# Voeding.net
KiCad netlist of a schematic drawn in Altium Designer
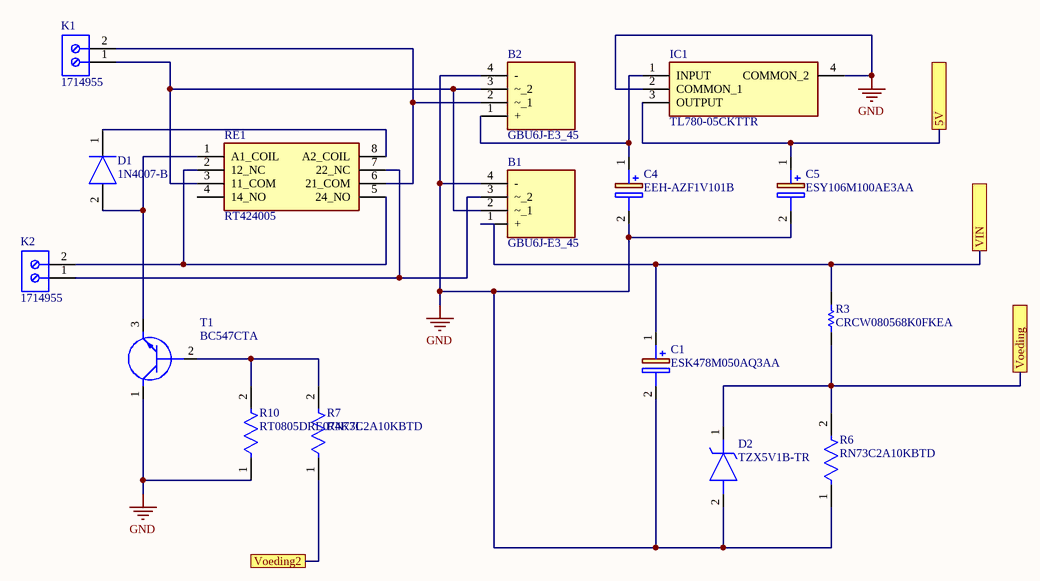
[diagram p0: Voeding.SchDoc]

(export (version "E")
  (design (tool "Eeschema 10.0.6"))
  (components
    (comp (ref "B1")
      (value "GBU6J-E3_45")
      (footprint "SamacSys:GBU6JE345")
      (description "Bridge Rectifier")
      (fields (field (name "MANUFACTURER_PART_NUMBER") "GBU6J-E3/45"))
      (libsource (lib "*") (part "GBU6J-E3_45"))
    )
    (comp (ref "B2")
      (value "GBU6J-E3_45")
      (footprint "SamacSys:GBU6JE345")
      (description "Bridge Rectifier")
      (fields (field (name "MANUFACTURER_PART_NUMBER") "GBU6J-E3/45"))
      (libsource (lib "*") (part "GBU6J-E3_45"))
    )
    (comp (ref "C1")
      (value "ESK478M050AQ3AA")
      (footprint "SamacSys:CAPPRD1000W80D2200H3700")
      (description "Capacitor Polarised")
      (fields (field (name "MOUSER2 PART NUMBER") "80-ESK478M050AQ3AA"))
      (libsource (lib "*") (part "ESK478M050AQ3AA"))
    )
    (comp (ref "C4")
      (value "EEH-AZF1V101B")
      (footprint "SamacSys:CAPPRD350W65D800H1050")
      (description "Capacitor Polarised")
      (libsource (lib "*") (part "EEH-AZF1V101B"))
    )
    (comp (ref "C5")
      (value "ESY106M100AE3AA")
      (footprint "SamacSys:CAPPRD250W50D630H1250")
      (description "Capacitor Polarised")
      (libsource (lib "*") (part "ESY106M100AE3AA"))
    )
    (comp (ref "D1")
      (value "1N4007-B")
      (footprint "SamacSys:DIOAD1410W90L470D235")
      (description "Diode")
      (libsource (lib "*") (part "1N4007-B"))
    )
    (comp (ref "D2")
      (value "TZX5V1B-TR")
      (footprint "SamacSys:DIOAD950W60L350D150")
      (description "Zener Diode")
      (libsource (lib "*") (part "TZX5V1B-TR"))
    )
    (comp (ref "IC1")
      (value "TL780-05CKTTR")
      (footprint "SamacSys:TL78005CKTTR")
      (description "Integrated Circuit")
      (libsource (lib "*") (part "TL780-05CKTTR"))
    )
    (comp (ref "K1")
      (value "1714955")
      (footprint "PHOE-1714955_V")
      (description "PC Terminal Block, Pitch 6.35 mm, 1 x 2 Position, Height 21.5 mm, Tail Lenght 5.1 mm, RoHS, Bulk")
      (fields (field (name "MANUFACTURER") "Phoenix Contact"))
      (libsource (lib "Altium Content Vault") (part "CN-1P-F-TB2"))
    )
    (comp (ref "K2")
      (value "1714955")
      (footprint "PHOE-1714955_V")
      (description "PC Terminal Block, Pitch 6.35 mm, 1 x 2 Position, Height 21.5 mm, Tail Lenght 5.1 mm, RoHS, Bulk")
      (fields (field (name "MANUFACTURER") "Phoenix Contact"))
      (libsource (lib "Altium Content Vault") (part "CN-1P-F-TB2"))
    )
    (comp (ref "R3")
      (value "CRCW080568K0FKEA")
      (footprint "RESC2013X50X30ML20T20")
      (fields (field (name "MANUFACTURER") "Vishay Dale"))
      (libsource (lib "Altium Content Vault") (part "RES"))
    )
    (comp (ref "R6")
      (value "RN73C2A10KBTD")
      (footprint "FP-RN732A-MFG")
      (description "SMD Chip Resistor, Thin Film, 10KΩ, 100 V, 0805 [2012 Metric], 100 mW, 0.1%, RN73 Series")
      (fields
        (field (name "MANUFACTURER") "TE Connectivity")
        (field (name "OCTOPART") "https://octopart.com/rn73c2a10kbtd-te+connectivity-22737006")
      )
      (libsource (lib "Altium Content Vault") (part "1029c3af85768c4190bb7ad29bc67b5"))
    )
    (comp (ref "R7")
      (value "RN73C2A10KBTD")
      (footprint "FP-RN732A-MFG")
      (description "SMD Chip Resistor, Thin Film, 10KΩ, 100 V, 0805 [2012 Metric], 100 mW, 0.1%, RN73 Series")
      (fields
        (field (name "MANUFACTURER") "TE Connectivity")
        (field (name "OCTOPART") "https://octopart.com/rn73c2a10kbtd-te+connectivity-22737006")
      )
      (libsource (lib "Altium Content Vault") (part "1029c3af85768c4190bb7ad29bc67b5"))
    )
    (comp (ref "R10")
      (value "RT0805DRE074K7L")
      (footprint "FP-RT0805-MFG")
      (description "RES SMD 4.7K OHM 0.5% 1/8W 0805")
      (fields
        (field (name "OCTOPART") "https://octopart.com/rt0805dre074k7l-yageo-1242027")
        (field (name "TOLERANCE") "0.01")
      )
      (libsource (lib "Altium Content Vault") (part "1029c3af85768c4190bb7ad29bc67b5"))
    )
    (comp (ref "RE1")
      (value "RT424005")
      (footprint "SamacSys:RT42")
      (description "Relay or Contactor")
      (fields (field (name "MOUSER2 PART NUMBER") "655-RT424005"))
      (libsource (lib "*") (part "RT424005"))
    )
    (comp (ref "T1")
      (value "BC547CTA")
      (footprint "SamacSys:MC79L15ACPG")
      (description "Transistor BJT NPN")
      (libsource (lib "*") (part "BC547CTA"))
    )
  )
  (nets
    (net (code "1") (name "/5V") (class "Default")
      (node (ref "C5") (pin "1") (pinfunction "+_1") (pintype "passive"))
      (node (ref "IC1") (pin "3") (pinfunction "OUTPUT_3") (pintype "passive"))
    )
    (net (code "2") (name "/VIN") (class "Default")
      (node (ref "B1") (pin "1") (pinfunction "+_1") (pintype "passive"))
      (node (ref "C1") (pin "1") (pinfunction "+_1") (pintype "passive"))
      (node (ref "R3") (pin "2") (pinfunction "2_2") (pintype "passive"))
    )
    (net (code "3") (name "/Voeding") (class "Default")
      (node (ref "D2") (pin "1") (pinfunction "K_1") (pintype "passive"))
      (node (ref "R3") (pin "1") (pinfunction "1_1") (pintype "passive"))
      (node (ref "R6") (pin "2") (pinfunction "2_2") (pintype "passive"))
    )
    (net (code "4") (name "/Voeding2") (class "Default")
      (node (ref "R7") (pin "1") (pinfunction "1_1") (pintype "passive"))
    )
    (net (code "5") (name "GND") (class "Default")
      (node (ref "B1") (pin "4") (pinfunction "-_4") (pintype "passive"))
      (node (ref "B2") (pin "4") (pinfunction "-_4") (pintype "passive"))
      (node (ref "C1") (pin "2") (pinfunction "-_2") (pintype "passive"))
      (node (ref "C4") (pin "2") (pinfunction "-_2") (pintype "passive"))
      (node (ref "C5") (pin "2") (pinfunction "-_2") (pintype "passive"))
      (node (ref "D2") (pin "2") (pinfunction "A_2") (pintype "passive"))
      (node (ref "IC1") (pin "2") (pinfunction "COMMON_1_2") (pintype "passive"))
      (node (ref "IC1") (pin "4") (pinfunction "COMMON_2_4") (pintype "passive"))
      (node (ref "R10") (pin "1") (pinfunction "1_1") (pintype "passive"))
      (node (ref "R6") (pin "1") (pinfunction "1_1") (pintype "passive"))
      (node (ref "T1") (pin "1") (pinfunction "C_1") (pintype "passive"))
    )
    (net (code "6") (name "Net-(B1-~_1)") (class "Default")
      (node (ref "B1") (pin "2") (pinfunction "~_1_2") (pintype "passive"))
      (node (ref "B2") (pin "3") (pinfunction "~_2_3") (pintype "passive"))
      (node (ref "K1") (pin "1") (pinfunction "1_1") (pintype "passive"))
      (node (ref "RE1") (pin "3") (pinfunction "11_COM_3") (pintype "passive"))
    )
    (net (code "7") (name "Net-(B1-~_2)") (class "Default")
      (node (ref "B1") (pin "3") (pinfunction "~_2_3") (pintype "passive"))
      (node (ref "K2") (pin "1") (pinfunction "1_1") (pintype "passive"))
      (node (ref "RE1") (pin "7") (pinfunction "22_NC_7") (pintype "passive"))
    )
    (net (code "8") (name "Net-(B2-+)") (class "Default")
      (node (ref "B2") (pin "1") (pinfunction "+_1") (pintype "passive"))
      (node (ref "C4") (pin "1") (pinfunction "+_1") (pintype "passive"))
      (node (ref "IC1") (pin "1") (pinfunction "INPUT_1") (pintype "passive"))
    )
    (net (code "9") (name "Net-(B2-~_1)") (class "Default")
      (node (ref "B2") (pin "2") (pinfunction "~_1_2") (pintype "passive"))
      (node (ref "K1") (pin "2") (pinfunction "2_2") (pintype "passive"))
      (node (ref "RE1") (pin "6") (pinfunction "21_COM_6") (pintype "passive"))
    )
    (net (code "10") (name "Net-(D1-A)") (class "Default")
      (node (ref "D1") (pin "2") (pinfunction "A_2") (pintype "passive"))
      (node (ref "RE1") (pin "1") (pinfunction "A1_COIL_1") (pintype "passive"))
      (node (ref "T1") (pin "3") (pinfunction "E_3") (pintype "passive"))
    )
    (net (code "11") (name "Net-(D1-K)") (class "Default")
      (node (ref "D1") (pin "1") (pinfunction "K_1") (pintype "passive"))
      (node (ref "RE1") (pin "8") (pinfunction "A2_COIL_8") (pintype "passive"))
    )
    (net (code "12") (name "Net-(RE1-12_NC)") (class "Default")
      (node (ref "K2") (pin "2") (pinfunction "2_2") (pintype "passive"))
      (node (ref "RE1") (pin "2") (pinfunction "12_NC_2") (pintype "passive"))
      (node (ref "RE1") (pin "5") (pinfunction "24_NO_5") (pintype "passive"))
    )
    (net (code "13") (name "Net-(T1-B)") (class "Default")
      (node (ref "R10") (pin "2") (pinfunction "2_2") (pintype "passive"))
      (node (ref "R7") (pin "2") (pinfunction "2_2") (pintype "passive"))
      (node (ref "T1") (pin "2") (pinfunction "B_2") (pintype "passive"))
    )
    (net (code "14") (name "unconnected-(RE1-14_NO-Pad4)") (class "Default")
      (node (ref "RE1") (pin "4") (pinfunction "14_NO_4") (pintype "passive"))
    )
  )
)
